# LowerMachine_test_v3_0.net
KiCad netlist of a schematic drawn in Altium Designer
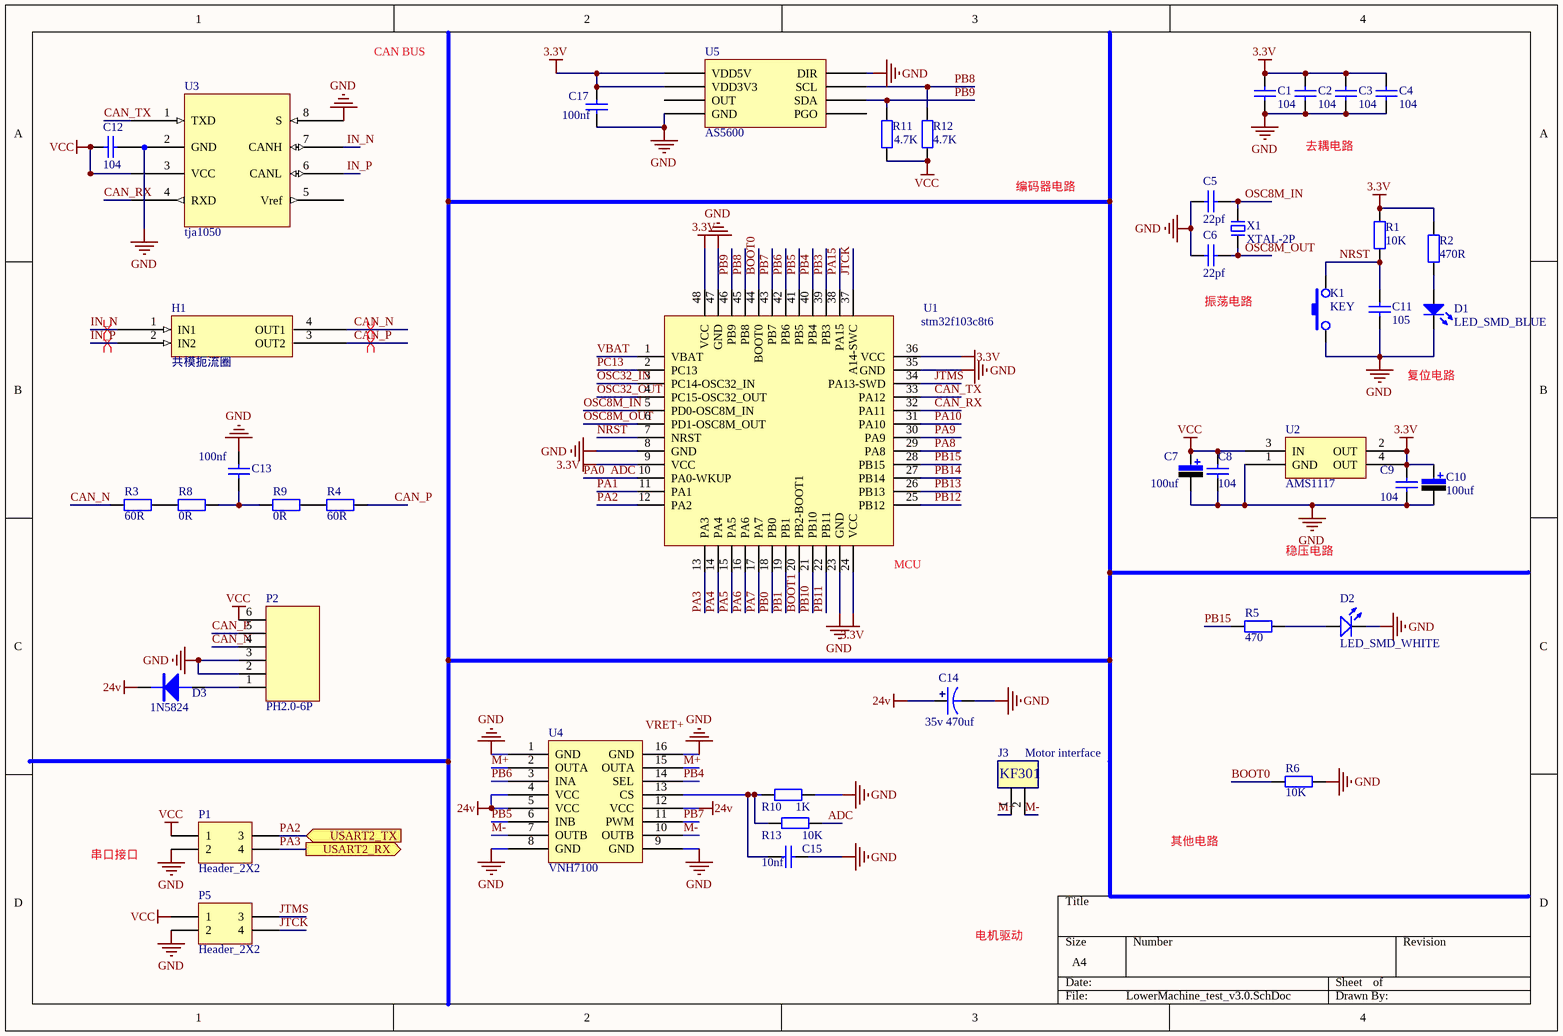
[diagram p0: LowerMachine_test_v3.0.SchDoc]

(export (version "E")
  (design (tool "Eeschema 10.0.6"))
  (components
    (comp (ref "C1") (value "104") (footprint "Cap-0603") (libsource (lib "最小系统元件库") (part "CAP")))
    (comp (ref "C2") (value "104") (footprint "Cap-0603") (libsource (lib "最小系统元件库") (part "CAP")))
    (comp (ref "C3") (value "104") (footprint "Cap-0603") (libsource (lib "最小系统元件库") (part "CAP")))
    (comp (ref "C4") (value "104") (footprint "Cap-0603") (libsource (lib "最小系统元件库") (part "CAP")))
    (comp (ref "C5") (value "22pf") (footprint "Cap-0603") (libsource (lib "最小系统元件库") (part "CAP")))
    (comp (ref "C6") (value "22pf") (footprint "Cap-0603") (libsource (lib "最小系统元件库") (part "CAP")))
    (comp (ref "C7") (value "100uf") (footprint "tan_cap_C") (libsource (lib "最小系统元件库") (part "tan_cap")))
    (comp (ref "C8") (value "104") (footprint "Cap-0603-M") (libsource (lib "最小系统元件库") (part "CAP")))
    (comp (ref "C9") (value "104") (footprint "Cap-0603-M") (libsource (lib "最小系统元件库") (part "CAP")))
    (comp (ref "C10") (value "100uf") (footprint "tan_cap_C") (libsource (lib "最小系统元件库") (part "tan_cap")))
    (comp (ref "C11") (value "105") (footprint "Cap-0603") (libsource (lib "最小系统元件库") (part "CAP")))
    (comp (ref "C12") (value "104") (footprint "Cap-0603") (libsource (lib "最小系统元件库") (part "CAP")))
    (comp (ref "C13") (value "100nf") (footprint "Cap-0603") (libsource (lib "最小系统元件库") (part "CAP")))
    (comp (ref "C14")
      (value "35v 470uf")
      (footprint "CAPE_G_10X10.3X10.2")
      (description "贴片电解电容")
      (libsource (lib "Miscellaneous Base") (part "CAPE-SMD"))
    )
    (comp (ref "C15")
      (value "10nf")
      (footprint "Cap-0603")
      (description "贴片陶瓷电容")
      (libsource (lib "Miscellaneous Base") (part "CAP"))
    )
    (comp (ref "C17")
      (value "100nf")
      (footprint "Cap-0603")
      (description "贴片陶瓷电容")
      (libsource (lib "Miscellaneous Base") (part "CAP"))
    )
    (comp (ref "D1")
      (value "LED_SMD_BLUE")
      (footprint "LED_0603_B")
      (description "发光二极管")
      (libsource (lib "Miscellaneous Transistor") (part "LED_SMD_BLUE"))
    )
    (comp (ref "D2")
      (value "LED_SMD_WHITE")
      (footprint "LED_0603_W")
      (description "发光二极管")
      (libsource (lib "Miscellaneous Transistor") (part "LED_SMD_WHITE"))
    )
    (comp (ref "D3")
      (value "1N5824")
      (footprint "DO-214AC/SMA")
      (description "普通二极管")
      (libsource (lib "Miscellaneous Transistor") (part "DIODE"))
    )
    (comp (ref "H1") (value "共模扼流圈") (footprint "共模扼流圈") (libsource (lib "CAN步进控制板元件库") (part "共模扼流圈")))
    (comp (ref "J3")
      (value "Motor interface")
      (footprint "KF301-5.0-2P")
      (libsource (lib "KF301") (part "KF301-2P"))
    )
    (comp (ref "K1")
      (value "KEY")
      (footprint "SW-SMD-2X4")
      (libsource (lib "Miscellaneous Switch") (part "KEY"))
    )
    (comp (ref "P1")
      (value "Header_2X2")
      (footprint "Header_SMD_2.54X2")
      (libsource (lib "Miscellaneous Header") (part "Header_2X2"))
    )
    (comp (ref "P2") (value "PH2.0-6P") (footprint "PH2.0S-6P") (libsource (lib "PH") (part "PH2.0-6P")))
    (comp (ref "P5")
      (value "Header_2X2")
      (footprint "Header_SMD_2.54X2")
      (libsource (lib "Miscellaneous Header") (part "Header_2X2"))
    )
    (comp (ref "R1")
      (value "10K")
      (footprint "Res-0603")
      (description "贴片电阻")
      (libsource (lib "") (part "RES_3"))
    )
    (comp (ref "R2")
      (value "470R")
      (footprint "Res-0603")
      (description "贴片电阻")
      (libsource (lib "") (part "RES_3"))
    )
    (comp (ref "R3")
      (value "60R")
      (footprint "Res-0603")
      (description "贴片电阻")
      (libsource (lib "") (part "RES_2"))
    )
    (comp (ref "R4")
      (value "60R")
      (footprint "Res-0603")
      (description "贴片电阻")
      (libsource (lib "") (part "RES_2"))
    )
    (comp (ref "R5")
      (value "470")
      (footprint "Res-0603")
      (description "贴片电阻")
      (libsource (lib "") (part "RES_2"))
    )
    (comp (ref "R6")
      (value "10K")
      (footprint "Res-0603")
      (description "贴片电阻")
      (libsource (lib "Miscellaneous Base") (part "RES"))
    )
    (comp (ref "R8")
      (value "0R")
      (footprint "Res-0603")
      (description "贴片电阻")
      (libsource (lib "") (part "RES_2"))
    )
    (comp (ref "R9")
      (value "0R")
      (footprint "Res-0603")
      (description "贴片电阻")
      (libsource (lib "") (part "RES_2"))
    )
    (comp (ref "R10")
      (value "1K")
      (footprint "Res-0603")
      (description "贴片电阻")
      (libsource (lib "Miscellaneous Base") (part "RES"))
    )
    (comp (ref "R11")
      (value "4.7K")
      (footprint "Res-0603")
      (description "贴片电阻")
      (libsource (lib "") (part "RES_1"))
    )
    (comp (ref "R12")
      (value "4.7K")
      (footprint "Res-0603")
      (description "贴片电阻")
      (libsource (lib "") (part "RES_1"))
    )
    (comp (ref "R13")
      (value "10K")
      (footprint "Res-0603")
      (description "贴片电阻")
      (libsource (lib "Miscellaneous Base") (part "RES"))
    )
    (comp (ref "U1")
      (value "stm32f103c8t6")
      (footprint "stm32f103c8t6")
      (libsource (lib "最小系统元件库") (part "stm32f103c8t6"))
    )
    (comp (ref "U2") (value "AMS1117") (footprint "AMS1117") (libsource (lib "最小系统元件库") (part "AMS1117")))
    (comp (ref "U3") (value "tja1050") (footprint "tja1050") (libsource (lib "CAN步进控制板元件库") (part "tja1050")))
    (comp (ref "U4") (value "VNH7100") (footprint "VNH7100") (libsource (lib "VNH7100") (part "VNH7100")))
    (comp (ref "U5")
      (value "AS5600")
      (footprint "AS5600")
      (libsource (lib "LowerMachineSchlib") (part "AS5600"))
    )
    (comp (ref "X1")
      (value "XTAL-2P")
      (footprint "OSC 5032-2P")
      (description "2脚无源脚晶振")
      (libsource (lib "Miscellaneous XTAL") (part "XTAL-2P"))
    )
  )
  (nets
    (net (code "1") (name "/ADC") (class "Default")
      (node (ref "R13") (pin "1") (pinfunction "1_1") (pintype "passive"))
      (node (ref "U1") (pin "10") (pinfunction "PA0-WKUP_10") (pintype "passive"))
    )
    (net (code "2") (name "/BOOT0") (class "Default")
      (node (ref "R6") (pin "2") (pinfunction "2_2") (pintype "passive"))
      (node (ref "U1") (pin "44") (pinfunction "BOOT0_44") (pintype "passive"))
    )
    (net (code "3") (name "/BOOT1") (class "Default")
      (node (ref "U1") (pin "20") (pinfunction "PB2-BOOT1_20") (pintype "passive"))
    )
    (net (code "4") (name "/CAN_N") (class "Default")
      (node (ref "H1") (pin "4") (pinfunction "OUT1_4") (pintype "passive"))
      (node (ref "P2") (pin "4") (pinfunction "4_4") (pintype "passive"))
      (node (ref "R3") (pin "1") (pinfunction "1_1") (pintype "passive"))
    )
    (net (code "5") (name "/CAN_P") (class "Default")
      (node (ref "H1") (pin "3") (pinfunction "OUT2_3") (pintype "passive"))
      (node (ref "P2") (pin "5") (pinfunction "5_5") (pintype "passive"))
      (node (ref "R4") (pin "2") (pinfunction "2_2") (pintype "passive"))
    )
    (net (code "6") (name "/CAN_RX") (class "Default")
      (node (ref "U1") (pin "32") (pinfunction "PA11_32") (pintype "passive"))
      (node (ref "U3") (pin "4") (pinfunction "RXD_4") (pintype "output"))
    )
    (net (code "7") (name "/CAN_TX") (class "Default")
      (node (ref "U1") (pin "33") (pinfunction "PA12_33") (pintype "passive"))
      (node (ref "U3") (pin "1") (pinfunction "TXD_1") (pintype "input"))
    )
    (net (code "8") (name "/IN_N") (class "Default")
      (node (ref "H1") (pin "1") (pinfunction "IN1_1") (pintype "input"))
      (node (ref "U3") (pin "7") (pinfunction "CANH_7") (pintype "bidirectional"))
    )
    (net (code "9") (name "/IN_P") (class "Default")
      (node (ref "H1") (pin "2") (pinfunction "IN2_2") (pintype "input"))
      (node (ref "U3") (pin "6") (pinfunction "CANL_6") (pintype "bidirectional"))
    )
    (net (code "10") (name "/JTCK") (class "Default")
      (node (ref "P5") (pin "4") (pinfunction "4_4") (pintype "passive"))
      (node (ref "U1") (pin "37") (pinfunction "A14-SWC_37") (pintype "passive"))
    )
    (net (code "11") (name "/JTMS") (class "Default")
      (node (ref "P5") (pin "3") (pinfunction "3_3") (pintype "passive"))
      (node (ref "U1") (pin "34") (pinfunction "PA13-SWD_34") (pintype "passive"))
    )
    (net (code "12") (name "/M+") (class "Default")
      (node (ref "J3") (pin "1") (pinfunction "1_1") (pintype "passive"))
      (node (ref "U4") (pin "15") (pinfunction "OUTA_15") (pintype "passive"))
      (node (ref "U4") (pin "2") (pinfunction "OUTA_2") (pintype "passive"))
    )
    (net (code "13") (name "/M-") (class "Default")
      (node (ref "J3") (pin "2") (pinfunction "2_2") (pintype "passive"))
      (node (ref "U4") (pin "10") (pinfunction "OUTB_10") (pintype "passive"))
      (node (ref "U4") (pin "7") (pinfunction "OUTB_7") (pintype "passive"))
    )
    (net (code "14") (name "/NRST") (class "Default")
      (node (ref "C11") (pin "2") (pinfunction "2_2") (pintype "passive"))
      (node (ref "K1") (pin "3") (pinfunction "3_3") (pintype "passive"))
      (node (ref "R1") (pin "2") (pinfunction "2_2") (pintype "passive"))
      (node (ref "U1") (pin "7") (pinfunction "NRST_7") (pintype "passive"))
    )
    (net (code "15") (name "/OSC8M_IN") (class "Default")
      (node (ref "C5") (pin "1") (pinfunction "1_1") (pintype "passive"))
      (node (ref "U1") (pin "5") (pinfunction "PD0-OSC8M_IN_5") (pintype "passive"))
      (node (ref "X1") (pin "2") (pinfunction "2_2") (pintype "passive"))
    )
    (net (code "16") (name "/OSC8M_OUT") (class "Default")
      (node (ref "C6") (pin "1") (pinfunction "1_1") (pintype "passive"))
      (node (ref "U1") (pin "6") (pinfunction "PD1-OSC8M_OUT_6") (pintype "passive"))
      (node (ref "X1") (pin "1") (pinfunction "1_1") (pintype "passive"))
    )
    (net (code "17") (name "/OSC32_IN") (class "Default")
      (node (ref "U1") (pin "3") (pinfunction "PC14-OSC32_IN_3") (pintype "passive"))
    )
    (net (code "18") (name "/OSC32_OUT") (class "Default")
      (node (ref "U1") (pin "4") (pinfunction "PC15-OSC32_OUT_4") (pintype "passive"))
    )
    (net (code "19") (name "/PA1") (class "Default")
      (node (ref "U1") (pin "11") (pinfunction "PA1_11") (pintype "passive"))
    )
    (net (code "20") (name "/PA2") (class "Default")
      (node (ref "P1") (pin "3") (pinfunction "3_3") (pintype "passive"))
      (node (ref "U1") (pin "12") (pinfunction "PA2_12") (pintype "passive"))
    )
    (net (code "21") (name "/PA3") (class "Default")
      (node (ref "P1") (pin "4") (pinfunction "4_4") (pintype "passive"))
      (node (ref "U1") (pin "13") (pinfunction "PA3_13") (pintype "passive"))
    )
    (net (code "22") (name "/PA4") (class "Default")
      (node (ref "U1") (pin "14") (pinfunction "PA4_14") (pintype "passive"))
    )
    (net (code "23") (name "/PA5") (class "Default")
      (node (ref "U1") (pin "15") (pinfunction "PA5_15") (pintype "passive"))
    )
    (net (code "24") (name "/PA6") (class "Default")
      (node (ref "U1") (pin "16") (pinfunction "PA6_16") (pintype "passive"))
    )
    (net (code "25") (name "/PA7") (class "Default")
      (node (ref "U1") (pin "17") (pinfunction "PA7_17") (pintype "passive"))
    )
    (net (code "26") (name "/PA8") (class "Default")
      (node (ref "U1") (pin "29") (pinfunction "PA8_29") (pintype "passive"))
    )
    (net (code "27") (name "/PA9") (class "Default")
      (node (ref "U1") (pin "30") (pinfunction "PA9_30") (pintype "passive"))
    )
    (net (code "28") (name "/PA10") (class "Default")
      (node (ref "U1") (pin "31") (pinfunction "PA10_31") (pintype "passive"))
    )
    (net (code "29") (name "/PA15") (class "Default")
      (node (ref "U1") (pin "38") (pinfunction "PA15_38") (pintype "passive"))
    )
    (net (code "30") (name "/PB0") (class "Default")
      (node (ref "U1") (pin "18") (pinfunction "PB0_18") (pintype "passive"))
    )
    (net (code "31") (name "/PB1") (class "Default")
      (node (ref "U1") (pin "19") (pinfunction "PB1_19") (pintype "passive"))
    )
    (net (code "32") (name "/PB3") (class "Default")
      (node (ref "U1") (pin "39") (pinfunction "PB3_39") (pintype "passive"))
    )
    (net (code "33") (name "/PB4") (class "Default")
      (node (ref "U1") (pin "40") (pinfunction "PB4_40") (pintype "passive"))
      (node (ref "U4") (pin "14") (pinfunction "SEL_14") (pintype "passive"))
    )
    (net (code "34") (name "/PB5") (class "Default")
      (node (ref "U1") (pin "41") (pinfunction "PB5_41") (pintype "passive"))
      (node (ref "U4") (pin "6") (pinfunction "INB_6") (pintype "passive"))
    )
    (net (code "35") (name "/PB6") (class "Default")
      (node (ref "U1") (pin "42") (pinfunction "PB6_42") (pintype "passive"))
      (node (ref "U4") (pin "3") (pinfunction "INA_3") (pintype "passive"))
    )
    (net (code "36") (name "/PB7") (class "Default")
      (node (ref "U1") (pin "43") (pinfunction "PB7_43") (pintype "passive"))
      (node (ref "U4") (pin "11") (pinfunction "PWM_11") (pintype "passive"))
    )
    (net (code "37") (name "/PB8") (class "Default")
      (node (ref "R12") (pin "2") (pinfunction "2_2") (pintype "passive"))
      (node (ref "U1") (pin "45") (pinfunction "PB8_45") (pintype "passive"))
      (node (ref "U5") (pin "7") (pinfunction "SCL_7") (pintype "passive"))
    )
    (net (code "38") (name "/PB9") (class "Default")
      (node (ref "R11") (pin "2") (pinfunction "2_2") (pintype "passive"))
      (node (ref "U1") (pin "46") (pinfunction "PB9_46") (pintype "passive"))
      (node (ref "U5") (pin "6") (pinfunction "SDA_6") (pintype "passive"))
    )
    (net (code "39") (name "/PB10") (class "Default")
      (node (ref "U1") (pin "21") (pinfunction "PB10_21") (pintype "passive"))
    )
    (net (code "40") (name "/PB11") (class "Default")
      (node (ref "U1") (pin "22") (pinfunction "PB11_22") (pintype "passive"))
    )
    (net (code "41") (name "/PB12") (class "Default")
      (node (ref "U1") (pin "25") (pinfunction "PB12_25") (pintype "passive"))
    )
    (net (code "42") (name "/PB13") (class "Default")
      (node (ref "U1") (pin "26") (pinfunction "PB13_26") (pintype "passive"))
    )
    (net (code "43") (name "/PB14") (class "Default")
      (node (ref "U1") (pin "27") (pinfunction "PB14_27") (pintype "passive"))
    )
    (net (code "44") (name "/PB15") (class "Default")
      (node (ref "R5") (pin "1") (pinfunction "1_1") (pintype "passive"))
      (node (ref "U1") (pin "28") (pinfunction "PB15_28") (pintype "passive"))
    )
    (net (code "45") (name "/PC13") (class "Default")
      (node (ref "U1") (pin "2") (pinfunction "PC13_2") (pintype "passive"))
    )
    (net (code "46") (name "/VBAT") (class "Default")
      (node (ref "U1") (pin "1") (pinfunction "VBAT_1") (pintype "passive"))
    )
    (net (code "48") (name "3.3V") (class "Default")
      (node (ref "C1") (pin "2") (pinfunction "2_2") (pintype "passive"))
      (node (ref "C10") (pin "1") (pinfunction "1_1") (pintype "passive"))
      (node (ref "C17") (pin "2") (pinfunction "2_2") (pintype "passive"))
      (node (ref "C2") (pin "2") (pinfunction "2_2") (pintype "passive"))
      (node (ref "C3") (pin "2") (pinfunction "2_2") (pintype "passive"))
      (node (ref "C4") (pin "2") (pinfunction "2_2") (pintype "passive"))
      (node (ref "C9") (pin "2") (pinfunction "2_2") (pintype "passive"))
      (node (ref "R1") (pin "1") (pinfunction "1_1") (pintype "passive"))
      (node (ref "R2") (pin "1") (pinfunction "1_1") (pintype "passive"))
      (node (ref "U1") (pin "24") (pinfunction "VCC_24") (pintype "passive"))
      (node (ref "U1") (pin "36") (pinfunction "VCC_36") (pintype "passive"))
      (node (ref "U1") (pin "48") (pinfunction "VCC_48") (pintype "passive"))
      (node (ref "U1") (pin "9") (pinfunction "VCC_9") (pintype "passive"))
      (node (ref "U2") (pin "2") (pinfunction "OUT_2") (pintype "passive"))
      (node (ref "U2") (pin "4") (pinfunction "OUT_4") (pintype "passive"))
      (node (ref "U5") (pin "1") (pinfunction "VDD5V_1") (pintype "passive"))
      (node (ref "U5") (pin "2") (pinfunction "VDD3V3_2") (pintype "passive"))
    )
    (net (code "49") (name "24v") (class "Default")
      (node (ref "C14") (pin "1") (pinfunction "1_1") (pintype "passive"))
      (node (ref "D3") (pin "K") (pinfunction "K_K") (pintype "passive"))
      (node (ref "U4") (pin "12") (pinfunction "VCC_12") (pintype "passive"))
      (node (ref "U4") (pin "4") (pinfunction "VCC_4") (pintype "passive"))
      (node (ref "U4") (pin "5") (pinfunction "VCC_5") (pintype "passive"))
    )
    (net (code "50") (name "GND") (class "Default")
      (node (ref "C1") (pin "1") (pinfunction "1_1") (pintype "passive"))
      (node (ref "C10") (pin "2") (pinfunction "2_2") (pintype "passive"))
      (node (ref "C11") (pin "1") (pinfunction "1_1") (pintype "passive"))
      (node (ref "C13") (pin "2") (pinfunction "2_2") (pintype "passive"))
      (node (ref "C14") (pin "2") (pinfunction "2_2") (pintype "passive"))
      (node (ref "C15") (pin "2") (pinfunction "2_2") (pintype "passive"))
      (node (ref "C17") (pin "1") (pinfunction "1_1") (pintype "passive"))
      (node (ref "C2") (pin "1") (pinfunction "1_1") (pintype "passive"))
      (node (ref "C3") (pin "1") (pinfunction "1_1") (pintype "passive"))
      (node (ref "C4") (pin "1") (pinfunction "1_1") (pintype "passive"))
      (node (ref "C5") (pin "2") (pinfunction "2_2") (pintype "passive"))
      (node (ref "C6") (pin "2") (pinfunction "2_2") (pintype "passive"))
      (node (ref "C7") (pin "2") (pinfunction "2_2") (pintype "passive"))
      (node (ref "C8") (pin "1") (pinfunction "1_1") (pintype "passive"))
      (node (ref "C9") (pin "1") (pinfunction "1_1") (pintype "passive"))
      (node (ref "D1") (pin "1") (pinfunction "K_1") (pintype "passive"))
      (node (ref "D2") (pin "1") (pinfunction "K_1") (pintype "passive"))
      (node (ref "K1") (pin "1") (pinfunction "1_1") (pintype "passive"))
      (node (ref "P1") (pin "2") (pinfunction "2_2") (pintype "passive"))
      (node (ref "P2") (pin "2") (pinfunction "2_2") (pintype "passive"))
      (node (ref "P2") (pin "3") (pinfunction "3_3") (pintype "passive"))
      (node (ref "P5") (pin "2") (pinfunction "2_2") (pintype "passive"))
      (node (ref "R10") (pin "1") (pinfunction "1_1") (pintype "passive"))
      (node (ref "R6") (pin "1") (pinfunction "1_1") (pintype "passive"))
      (node (ref "U1") (pin "23") (pinfunction "GND_23") (pintype "passive"))
      (node (ref "U1") (pin "35") (pinfunction "GND_35") (pintype "passive"))
      (node (ref "U1") (pin "47") (pinfunction "GND_47") (pintype "passive"))
      (node (ref "U1") (pin "8") (pinfunction "GND_8") (pintype "passive"))
      (node (ref "U2") (pin "1") (pinfunction "GND_1") (pintype "passive"))
      (node (ref "U3") (pin "8") (pinfunction "S_8") (pintype "input"))
      (node (ref "U4") (pin "1") (pinfunction "GND_1") (pintype "passive"))
      (node (ref "U4") (pin "16") (pinfunction "GND_16") (pintype "passive"))
      (node (ref "U4") (pin "8") (pinfunction "GND_8") (pintype "passive"))
      (node (ref "U4") (pin "9") (pinfunction "GND_9") (pintype "passive"))
      (node (ref "U5") (pin "4") (pinfunction "GND_4") (pintype "passive"))
      (node (ref "U5") (pin "8") (pinfunction "DIR_8") (pintype "passive"))
    )
    (net (code "51") (name "Net-(C13-Pad1)") (class "Default")
      (node (ref "C13") (pin "1") (pinfunction "1_1") (pintype "passive"))
      (node (ref "R8") (pin "2") (pinfunction "2_2") (pintype "passive"))
      (node (ref "R9") (pin "1") (pinfunction "1_1") (pintype "passive"))
    )
    (net (code "52") (name "Net-(D1-A)") (class "Default")
      (node (ref "D1") (pin "2") (pinfunction "A_2") (pintype "passive"))
      (node (ref "R2") (pin "2") (pinfunction "2_2") (pintype "passive"))
    )
    (net (code "53") (name "Net-(D2-A)") (class "Default")
      (node (ref "D2") (pin "2") (pinfunction "A_2") (pintype "passive"))
      (node (ref "R5") (pin "2") (pinfunction "2_2") (pintype "passive"))
    )
    (net (code "54") (name "Net-(D3-PadA)") (class "Default")
      (node (ref "D3") (pin "A") (pinfunction "A_A") (pintype "passive"))
      (node (ref "P2") (pin "1") (pinfunction "1_1") (pintype "passive"))
    )
    (net (code "55") (name "Net-(R3-Pad2)") (class "Default")
      (node (ref "R3") (pin "2") (pinfunction "2_2") (pintype "passive"))
      (node (ref "R8") (pin "1") (pinfunction "1_1") (pintype "passive"))
    )
    (net (code "56") (name "Net-(R4-Pad1)") (class "Default")
      (node (ref "R4") (pin "1") (pinfunction "1_1") (pintype "passive"))
      (node (ref "R9") (pin "2") (pinfunction "2_2") (pintype "passive"))
    )
    (net (code "57") (name "Net-(U3-GND)") (class "Default")
      (node (ref "C12") (pin "2") (pinfunction "2_2") (pintype "passive"))
      (node (ref "U3") (pin "2") (pinfunction "GND_2") (pintype "power_in"))
    )
    (net (code "58") (name "Net-(U4-CS)") (class "Default")
      (node (ref "C15") (pin "1") (pinfunction "1_1") (pintype "passive"))
      (node (ref "R10") (pin "2") (pinfunction "2_2") (pintype "passive"))
      (node (ref "R13") (pin "2") (pinfunction "2_2") (pintype "passive"))
      (node (ref "U4") (pin "13") (pinfunction "CS_13") (pintype "passive"))
    )
    (net (code "59") (name "VCC") (class "Default")
      (node (ref "C12") (pin "1") (pinfunction "1_1") (pintype "passive"))
      (node (ref "C7") (pin "1") (pinfunction "1_1") (pintype "passive"))
      (node (ref "C8") (pin "2") (pinfunction "2_2") (pintype "passive"))
      (node (ref "P1") (pin "1") (pinfunction "1_1") (pintype "passive"))
      (node (ref "P2") (pin "6") (pinfunction "6_6") (pintype "passive"))
      (node (ref "P5") (pin "1") (pinfunction "1_1") (pintype "passive"))
      (node (ref "R11") (pin "1") (pinfunction "1_1") (pintype "passive"))
      (node (ref "R12") (pin "1") (pinfunction "1_1") (pintype "passive"))
      (node (ref "U2") (pin "3") (pinfunction "IN_3") (pintype "passive"))
      (node (ref "U3") (pin "3") (pinfunction "VCC_3") (pintype "power_in"))
    )
    (net (code "60") (name "unconnected-(U3-Vref-Pad5)") (class "Default")
      (node (ref "U3") (pin "5") (pinfunction "Vref_5") (pintype "output"))
    )
    (net (code "61") (name "unconnected-(U5-OUT-Pad3)") (class "Default")
      (node (ref "U5") (pin "3") (pinfunction "OUT_3") (pintype "passive"))
    )
    (net (code "62") (name "unconnected-(U5-PGO-Pad5)") (class "Default")
      (node (ref "U5") (pin "5") (pinfunction "PGO_5") (pintype "passive"))
    )
  )
)
